# adapter.net
KiCad netlist of a schematic drawn in EAGLE
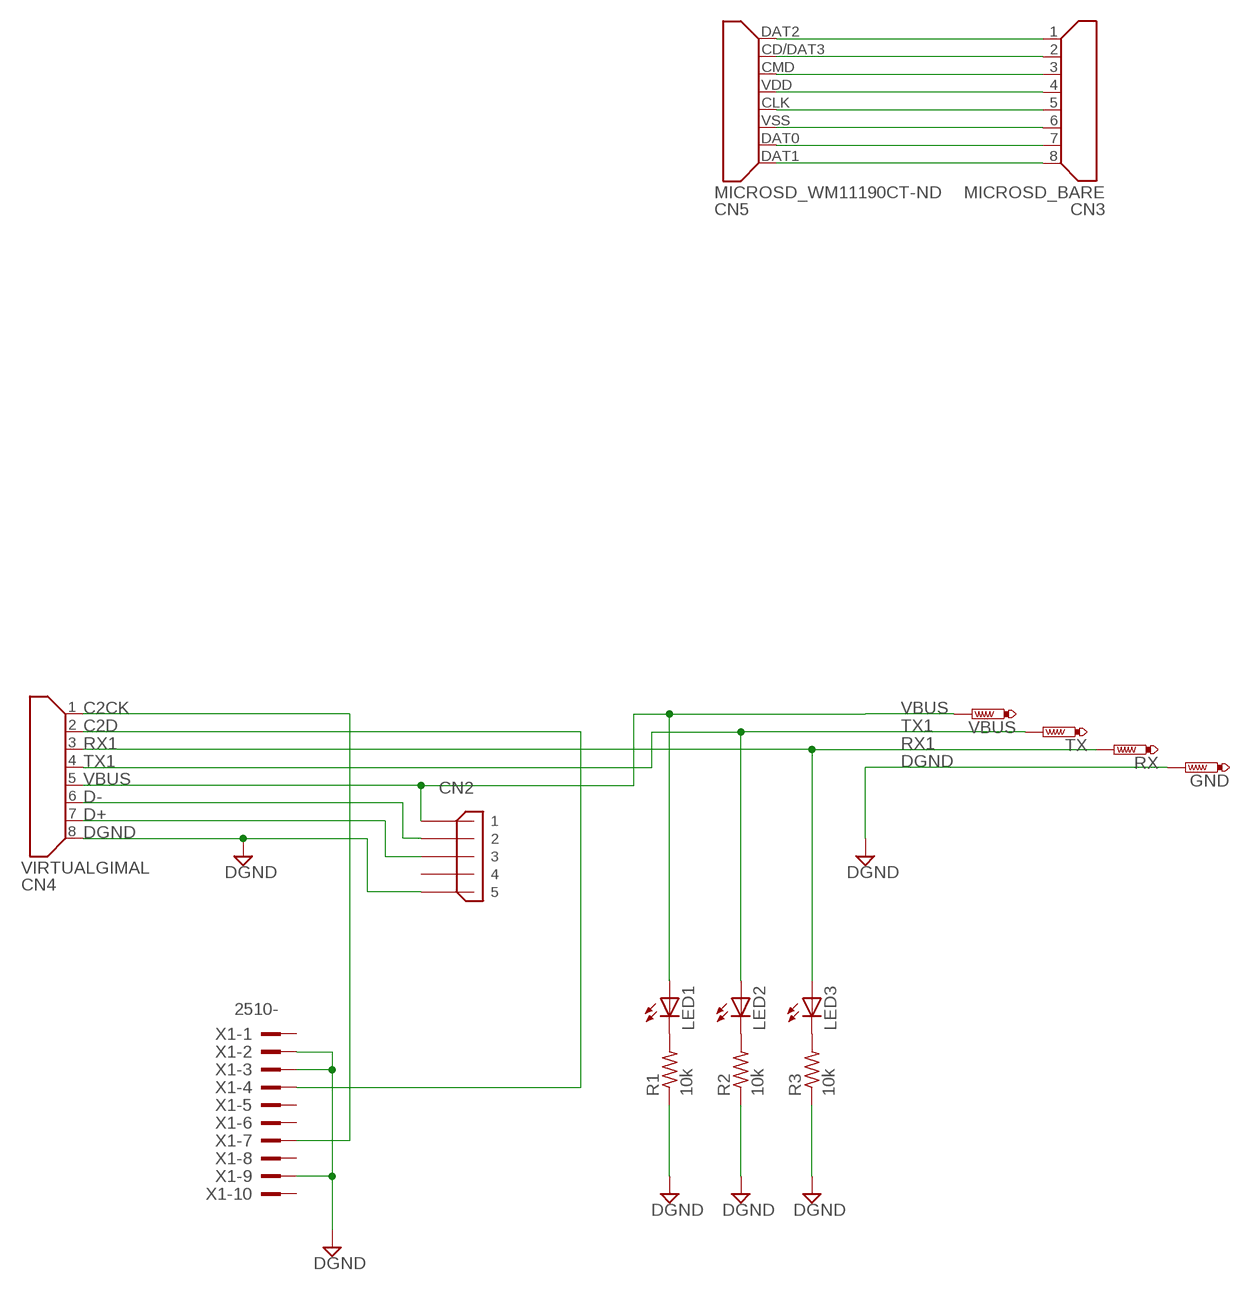
[diagram p0: schematic, sheet 1]

(export (version "E")
  (design (tool "Eeschema 10.0.6"))
  (components
    (comp (ref "CN2")
      (value "MICROUSB_ZX62D1-B-5PA(30)")
      (footprint "eagle-import:ZX62D1-B-5PA(30)")
      (libsource (lib "eagle-import") (part "MICROUSB_ZX62D1-B-5PA(30)"))
    )
    (comp (ref "CN3")
      (value "MICROSD_BARE")
      (footprint "eagle-import:MICROSD")
      (libsource (lib "eagle-import") (part "MICROSD_BARE"))
    )
    (comp (ref "CN4")
      (value "VIRTUALGIMAL")
      (footprint "eagle-import:VIRTUALGIMBAL")
      (libsource (lib "eagle-import") (part "VIRTUALGIMAL"))
    )
    (comp (ref "CN5")
      (value "MICROSD_WM11190CT-ND")
      (footprint "eagle-import:5033981892")
      (libsource (lib "eagle-import") (part "MICROSD_WM11190CT-ND"))
    )
    (comp (ref "GND")
      (value "PTR1TP19R")
      (footprint "eagle-import:TP19R")
      (libsource (lib "eagle-import") (part "PTR1TP19R"))
    )
    (comp (ref "LED1")
      (value "LEDSML0603")
      (footprint "eagle-import:SML0603")
      (libsource (lib "eagle-import") (part "LEDSML0603"))
    )
    (comp (ref "LED2")
      (value "LEDSML0603")
      (footprint "eagle-import:SML0603")
      (libsource (lib "eagle-import") (part "LEDSML0603"))
    )
    (comp (ref "LED3")
      (value "LEDSML0603")
      (footprint "eagle-import:SML0603")
      (libsource (lib "eagle-import") (part "LEDSML0603"))
    )
    (comp (ref "R1")
      (value "10k")
      (footprint "eagle-import:R0402")
      (libsource (lib "eagle-import") (part "R-US_R0402"))
    )
    (comp (ref "R2")
      (value "10k")
      (footprint "eagle-import:R0402")
      (libsource (lib "eagle-import") (part "R-US_R0402"))
    )
    (comp (ref "R3")
      (value "10k")
      (footprint "eagle-import:R0402")
      (libsource (lib "eagle-import") (part "R-US_R0402"))
    )
    (comp (ref "RX")
      (value "PTR1TP19R")
      (footprint "eagle-import:TP19R")
      (libsource (lib "eagle-import") (part "PTR1TP19R"))
    )
    (comp (ref "TX")
      (value "PTR1TP19R")
      (footprint "eagle-import:TP19R")
      (libsource (lib "eagle-import") (part "PTR1TP19R"))
    )
    (comp (ref "VBUS")
      (value "PTR1TP19R")
      (footprint "eagle-import:TP19R")
      (libsource (lib "eagle-import") (part "PTR1TP19R"))
    )
    (comp (ref "X1")
      (value "2510-")
      (footprint "eagle-import:PAK100_2500-10")
      (fields (field (name "MF") "3M") (field (name "MPN") "2510-6002UB"))
      (libsource (lib "eagle-import") (part "2510-"))
    )
  )
  (nets
    (net (code "1") (name "/C2CK") (class "Default")
      (node (ref "CN4") (pin "1") (pinfunction "P$1_1") (pintype "passive"))
      (node (ref "X1") (pin "7") (pinfunction "KL_7") (pintype "passive"))
    )
    (net (code "2") (name "/C2D") (class "Default")
      (node (ref "CN4") (pin "2") (pinfunction "P$2_2") (pintype "passive"))
      (node (ref "X1") (pin "4") (pinfunction "KL_4") (pintype "passive"))
    )
    (net (code "3") (name "/D+") (class "Default")
      (node (ref "CN2") (pin "3_D+") (pinfunction "3_3_D+") (pintype "input"))
      (node (ref "CN4") (pin "7") (pinfunction "P$7_7") (pintype "passive"))
    )
    (net (code "4") (name "/D-") (class "Default")
      (node (ref "CN2") (pin "2_D-") (pinfunction "2_2_D-") (pintype "input"))
      (node (ref "CN4") (pin "6") (pinfunction "P$6_6") (pintype "passive"))
    )
    (net (code "5") (name "/RX1") (class "Default")
      (node (ref "CN4") (pin "3") (pinfunction "P$3_3") (pintype "passive"))
      (node (ref "LED3") (pin "A") (pinfunction "A_A") (pintype "passive"))
      (node (ref "RX") (pin "TP") (pinfunction "TP_TP") (pintype "input"))
    )
    (net (code "6") (name "/TX1") (class "Default")
      (node (ref "CN4") (pin "4") (pinfunction "P$4_4") (pintype "passive"))
      (node (ref "LED2") (pin "A") (pinfunction "A_A") (pintype "passive"))
      (node (ref "TX") (pin "TP") (pinfunction "TP_TP") (pintype "input"))
    )
    (net (code "7") (name "/VBUS") (class "Default")
      (node (ref "CN2") (pin "1_VCC") (pinfunction "1_1_VCC") (pintype "input"))
      (node (ref "CN4") (pin "5") (pinfunction "P$5_5") (pintype "passive"))
      (node (ref "LED1") (pin "A") (pinfunction "A_A") (pintype "passive"))
      (node (ref "VBUS") (pin "TP") (pinfunction "TP_TP") (pintype "input"))
    )
    (net (code "8") (name "DGND") (class "Default")
      (node (ref "CN2") (pin "5_GND") (pinfunction "5_5_GND") (pintype "input"))
      (node (ref "CN4") (pin "8") (pinfunction "P$8_8") (pintype "passive"))
      (node (ref "GND") (pin "TP") (pinfunction "TP_TP") (pintype "input"))
      (node (ref "R1") (pin "1") (pinfunction "1_1") (pintype "passive"))
      (node (ref "R2") (pin "1") (pinfunction "1_1") (pintype "passive"))
      (node (ref "R3") (pin "1") (pinfunction "1_1") (pintype "passive"))
      (node (ref "X1") (pin "2") (pinfunction "KL_2") (pintype "passive"))
      (node (ref "X1") (pin "3") (pinfunction "KL_3") (pintype "passive"))
      (node (ref "X1") (pin "9") (pinfunction "KL_9") (pintype "passive"))
    )
    (net (code "9") (name "Net-(CN3-P$1)") (class "Default")
      (node (ref "CN3") (pin "1") (pinfunction "P$1_1") (pintype "passive"))
      (node (ref "CN5") (pin "DAT2") (pinfunction "P$1_DAT2") (pintype "passive"))
    )
    (net (code "10") (name "Net-(CN3-P$2)") (class "Default")
      (node (ref "CN3") (pin "2") (pinfunction "P$2_2") (pintype "passive"))
      (node (ref "CN5") (pin "CD/DAT3") (pinfunction "P$2_CD/DAT3") (pintype "passive"))
    )
    (net (code "11") (name "Net-(CN3-P$3)") (class "Default")
      (node (ref "CN3") (pin "3") (pinfunction "P$3_3") (pintype "passive"))
      (node (ref "CN5") (pin "CMD") (pinfunction "P$3_CMD") (pintype "passive"))
    )
    (net (code "12") (name "Net-(CN3-P$4)") (class "Default")
      (node (ref "CN3") (pin "4") (pinfunction "P$4_4") (pintype "passive"))
      (node (ref "CN5") (pin "VDD") (pinfunction "P$4_VDD") (pintype "passive"))
    )
    (net (code "13") (name "Net-(CN3-P$5)") (class "Default")
      (node (ref "CN3") (pin "5") (pinfunction "P$5_5") (pintype "passive"))
      (node (ref "CN5") (pin "CLK") (pinfunction "P$5_CLK") (pintype "passive"))
    )
    (net (code "14") (name "Net-(CN3-P$6)") (class "Default")
      (node (ref "CN3") (pin "6") (pinfunction "P$6_6") (pintype "passive"))
      (node (ref "CN5") (pin "VSS") (pinfunction "P$6_VSS") (pintype "passive"))
    )
    (net (code "15") (name "Net-(CN3-P$7)") (class "Default")
      (node (ref "CN3") (pin "7") (pinfunction "P$7_7") (pintype "passive"))
      (node (ref "CN5") (pin "DAT0") (pinfunction "P$7_DAT0") (pintype "passive"))
    )
    (net (code "16") (name "Net-(CN3-P$8)") (class "Default")
      (node (ref "CN3") (pin "8") (pinfunction "P$8_8") (pintype "passive"))
      (node (ref "CN5") (pin "DAT1") (pinfunction "P$8_DAT1") (pintype "passive"))
    )
    (net (code "17") (name "Net-(LED1-PadC)") (class "Default")
      (node (ref "LED1") (pin "C") (pinfunction "C_C") (pintype "passive"))
      (node (ref "R1") (pin "2") (pinfunction "2_2") (pintype "passive"))
    )
    (net (code "18") (name "Net-(LED2-PadC)") (class "Default")
      (node (ref "LED2") (pin "C") (pinfunction "C_C") (pintype "passive"))
      (node (ref "R2") (pin "2") (pinfunction "2_2") (pintype "passive"))
    )
    (net (code "19") (name "Net-(LED3-PadC)") (class "Default")
      (node (ref "LED3") (pin "C") (pinfunction "C_C") (pintype "passive"))
      (node (ref "R3") (pin "2") (pinfunction "2_2") (pintype "passive"))
    )
    (net (code "20") (name "unconnected-(CN2-4-Pad4_ID)") (class "Default")
      (node (ref "CN2") (pin "4_ID") (pinfunction "4_4_ID") (pintype "input"))
    )
    (net (code "21") (name "unconnected-(X1A-KL-Pad1)") (class "Default")
      (node (ref "X1") (pin "1") (pinfunction "KL_1") (pintype "passive"))
    )
    (net (code "22") (name "unconnected-(X1B-KL-Pad10)") (class "Default")
      (node (ref "X1") (pin "10") (pinfunction "KL_10") (pintype "passive"))
    )
    (net (code "23") (name "unconnected-(X1F-KL-Pad5)") (class "Default")
      (node (ref "X1") (pin "5") (pinfunction "KL_5") (pintype "passive"))
    )
    (net (code "24") (name "unconnected-(X1G-KL-Pad6)") (class "Default")
      (node (ref "X1") (pin "6") (pinfunction "KL_6") (pintype "passive"))
    )
    (net (code "25") (name "unconnected-(X1I-KL-Pad8)") (class "Default")
      (node (ref "X1") (pin "8") (pinfunction "KL_8") (pintype "passive"))
    )
  )
)
